# Eshaan_-_DIYpiano.net
KiCad netlist of a schematic drawn in EAGLE
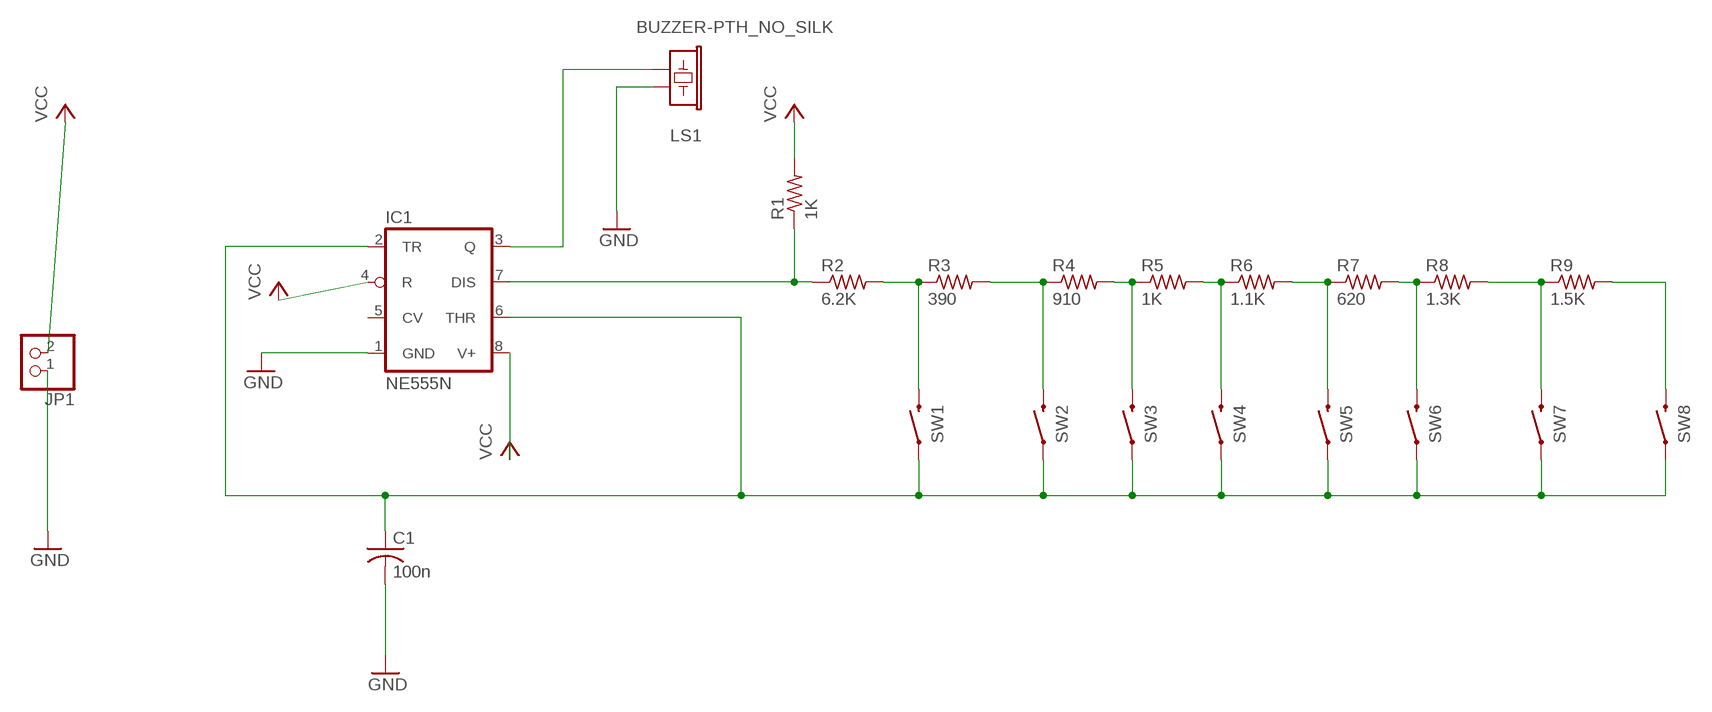
[diagram p0: schematic, sheet 1]

(export (version "E")
  (design (tool "Eeschema 10.0.6"))
  (components
    (comp (ref "C1")
      (value "100n")
      (footprint "eagle-import:C025-025X050")
      (libsource (lib "eagle-import") (part "C-US025-025X050"))
    )
    (comp (ref "IC1")
      (value "NE555N")
      (footprint "eagle-import:DIL08")
      (libsource (lib "eagle-import") (part "555NNE"))
    )
    (comp (ref "JP1")
      (value "PINHD-1X2")
      (footprint "eagle-import:1X02")
      (libsource (lib "eagle-import") (part "PINHD-1X2"))
    )
    (comp (ref "LS1")
      (value "BUZZER-PTH_NO_SILK")
      (footprint "eagle-import:BUZZER-12MM-NS")
      (libsource (lib "eagle-import") (part "BUZZER-PTH_NO_SILK"))
    )
    (comp (ref "R1")
      (value "1K")
      (footprint "eagle-import:0207_10")
      (libsource (lib "eagle-import") (part "R-US_0207/10"))
    )
    (comp (ref "R2")
      (value "6.2K")
      (footprint "eagle-import:0207_10")
      (libsource (lib "eagle-import") (part "R-US_0207/10"))
    )
    (comp (ref "R3")
      (value "390")
      (footprint "eagle-import:0207_10")
      (libsource (lib "eagle-import") (part "R-US_0207/10"))
    )
    (comp (ref "R4")
      (value "910")
      (footprint "eagle-import:0207_10")
      (libsource (lib "eagle-import") (part "R-US_0207/10"))
    )
    (comp (ref "R5")
      (value "1K")
      (footprint "eagle-import:0207_10")
      (libsource (lib "eagle-import") (part "R-US_0207/10"))
    )
    (comp (ref "R6")
      (value "1.1K")
      (footprint "eagle-import:0207_10")
      (libsource (lib "eagle-import") (part "R-US_0207/10"))
    )
    (comp (ref "R7")
      (value "620")
      (footprint "eagle-import:0207_10")
      (libsource (lib "eagle-import") (part "R-US_0207/10"))
    )
    (comp (ref "R8")
      (value "1.3K")
      (footprint "eagle-import:0207_10")
      (libsource (lib "eagle-import") (part "R-US_0207/10"))
    )
    (comp (ref "R9")
      (value "1.5K")
      (footprint "eagle-import:0207_10")
      (libsource (lib "eagle-import") (part "R-US_0207/10"))
    )
    (comp (ref "SW1")
      (value "MOMENTARY-SWITCH-SPST-PTH-6.0MM")
      (footprint "eagle-import:TACTILE_SWITCH_PTH_6.0MM")
      (libsource (lib "eagle-import") (part "MOMENTARY-SWITCH-SPST-PTH-6.0MM"))
    )
    (comp (ref "SW2")
      (value "MOMENTARY-SWITCH-SPST-PTH-6.0MM")
      (footprint "eagle-import:TACTILE_SWITCH_PTH_6.0MM")
      (libsource (lib "eagle-import") (part "MOMENTARY-SWITCH-SPST-PTH-6.0MM"))
    )
    (comp (ref "SW3")
      (value "MOMENTARY-SWITCH-SPST-PTH-6.0MM")
      (footprint "eagle-import:TACTILE_SWITCH_PTH_6.0MM")
      (libsource (lib "eagle-import") (part "MOMENTARY-SWITCH-SPST-PTH-6.0MM"))
    )
    (comp (ref "SW4")
      (value "MOMENTARY-SWITCH-SPST-PTH-6.0MM")
      (footprint "eagle-import:TACTILE_SWITCH_PTH_6.0MM")
      (libsource (lib "eagle-import") (part "MOMENTARY-SWITCH-SPST-PTH-6.0MM"))
    )
    (comp (ref "SW5")
      (value "MOMENTARY-SWITCH-SPST-PTH-6.0MM")
      (footprint "eagle-import:TACTILE_SWITCH_PTH_6.0MM")
      (libsource (lib "eagle-import") (part "MOMENTARY-SWITCH-SPST-PTH-6.0MM"))
    )
    (comp (ref "SW6")
      (value "MOMENTARY-SWITCH-SPST-PTH-6.0MM")
      (footprint "eagle-import:TACTILE_SWITCH_PTH_6.0MM")
      (libsource (lib "eagle-import") (part "MOMENTARY-SWITCH-SPST-PTH-6.0MM"))
    )
    (comp (ref "SW7")
      (value "MOMENTARY-SWITCH-SPST-PTH-6.0MM")
      (footprint "eagle-import:TACTILE_SWITCH_PTH_6.0MM")
      (libsource (lib "eagle-import") (part "MOMENTARY-SWITCH-SPST-PTH-6.0MM"))
    )
    (comp (ref "SW8")
      (value "MOMENTARY-SWITCH-SPST-PTH-6.0MM")
      (footprint "eagle-import:TACTILE_SWITCH_PTH_6.0MM")
      (libsource (lib "eagle-import") (part "MOMENTARY-SWITCH-SPST-PTH-6.0MM"))
    )
  )
  (nets
    (net (code "1") (name "GND") (class "Default")
      (node (ref "C1") (pin "2") (pinfunction "2_2") (pintype "passive"))
      (node (ref "IC1") (pin "1") (pinfunction "GND_1") (pintype "power_in"))
      (node (ref "JP1") (pin "1") (pinfunction "1_1") (pintype "passive"))
      (node (ref "LS1") (pin "-") (pinfunction "2_-") (pintype "passive"))
    )
    (net (code "2") (name "Net-(IC1-DIS)") (class "Default")
      (node (ref "IC1") (pin "7") (pinfunction "DIS_7") (pintype "input"))
      (node (ref "R1") (pin "1") (pinfunction "1_1") (pintype "passive"))
      (node (ref "R2") (pin "1") (pinfunction "1_1") (pintype "passive"))
    )
    (net (code "3") (name "Net-(IC1-Q)") (class "Default")
      (node (ref "IC1") (pin "3") (pinfunction "Q_3") (pintype "output"))
      (node (ref "LS1") (pin "+") (pinfunction "1_+") (pintype "passive"))
    )
    (net (code "4") (name "Net-(IC1-THR)") (class "Default")
      (node (ref "C1") (pin "1") (pinfunction "1_1") (pintype "passive"))
      (node (ref "IC1") (pin "2") (pinfunction "TR_2") (pintype "input"))
      (node (ref "IC1") (pin "6") (pinfunction "THR_6") (pintype "input"))
      (node (ref "SW1") (pin "1") (pinfunction "1_1") (pintype "passive"))
      (node (ref "SW2") (pin "1") (pinfunction "1_1") (pintype "passive"))
      (node (ref "SW3") (pin "1") (pinfunction "1_1") (pintype "passive"))
      (node (ref "SW4") (pin "1") (pinfunction "1_1") (pintype "passive"))
      (node (ref "SW5") (pin "1") (pinfunction "1_1") (pintype "passive"))
      (node (ref "SW6") (pin "1") (pinfunction "1_1") (pintype "passive"))
      (node (ref "SW7") (pin "1") (pinfunction "1_1") (pintype "passive"))
      (node (ref "SW8") (pin "1") (pinfunction "1_1") (pintype "passive"))
    )
    (net (code "5") (name "Net-(SW1-2)") (class "Default")
      (node (ref "R2") (pin "2") (pinfunction "2_2") (pintype "passive"))
      (node (ref "R3") (pin "1") (pinfunction "1_1") (pintype "passive"))
      (node (ref "SW1") (pin "3") (pinfunction "2_3") (pintype "passive"))
    )
    (net (code "6") (name "Net-(SW2-2)") (class "Default")
      (node (ref "R3") (pin "2") (pinfunction "2_2") (pintype "passive"))
      (node (ref "R4") (pin "1") (pinfunction "1_1") (pintype "passive"))
      (node (ref "SW2") (pin "3") (pinfunction "2_3") (pintype "passive"))
    )
    (net (code "7") (name "Net-(SW3-2)") (class "Default")
      (node (ref "R4") (pin "2") (pinfunction "2_2") (pintype "passive"))
      (node (ref "R5") (pin "1") (pinfunction "1_1") (pintype "passive"))
      (node (ref "SW3") (pin "3") (pinfunction "2_3") (pintype "passive"))
    )
    (net (code "8") (name "Net-(SW4-2)") (class "Default")
      (node (ref "R5") (pin "2") (pinfunction "2_2") (pintype "passive"))
      (node (ref "R6") (pin "1") (pinfunction "1_1") (pintype "passive"))
      (node (ref "SW4") (pin "3") (pinfunction "2_3") (pintype "passive"))
    )
    (net (code "9") (name "Net-(SW5-2)") (class "Default")
      (node (ref "R6") (pin "2") (pinfunction "2_2") (pintype "passive"))
      (node (ref "R7") (pin "1") (pinfunction "1_1") (pintype "passive"))
      (node (ref "SW5") (pin "3") (pinfunction "2_3") (pintype "passive"))
    )
    (net (code "10") (name "Net-(SW6-2)") (class "Default")
      (node (ref "R7") (pin "2") (pinfunction "2_2") (pintype "passive"))
      (node (ref "R8") (pin "1") (pinfunction "1_1") (pintype "passive"))
      (node (ref "SW6") (pin "3") (pinfunction "2_3") (pintype "passive"))
    )
    (net (code "11") (name "Net-(SW7-2)") (class "Default")
      (node (ref "R8") (pin "2") (pinfunction "2_2") (pintype "passive"))
      (node (ref "R9") (pin "1") (pinfunction "1_1") (pintype "passive"))
      (node (ref "SW7") (pin "3") (pinfunction "2_3") (pintype "passive"))
    )
    (net (code "12") (name "Net-(SW8-2)") (class "Default")
      (node (ref "R9") (pin "2") (pinfunction "2_2") (pintype "passive"))
      (node (ref "SW8") (pin "3") (pinfunction "2_3") (pintype "passive"))
    )
    (net (code "13") (name "VCC") (class "Default")
      (node (ref "IC1") (pin "4") (pinfunction "R_4") (pintype "input"))
      (node (ref "IC1") (pin "8") (pinfunction "V+_8") (pintype "power_in"))
      (node (ref "JP1") (pin "2") (pinfunction "2_2") (pintype "passive"))
      (node (ref "R1") (pin "2") (pinfunction "2_2") (pintype "passive"))
    )
    (net (code "14") (name "unconnected-(IC1-CV-Pad5)") (class "Default")
      (node (ref "IC1") (pin "5") (pinfunction "CV_5") (pintype "input"))
    )
  )
)
